# OperantFEDv2.net
KiCad netlist of a schematic drawn in EAGLE
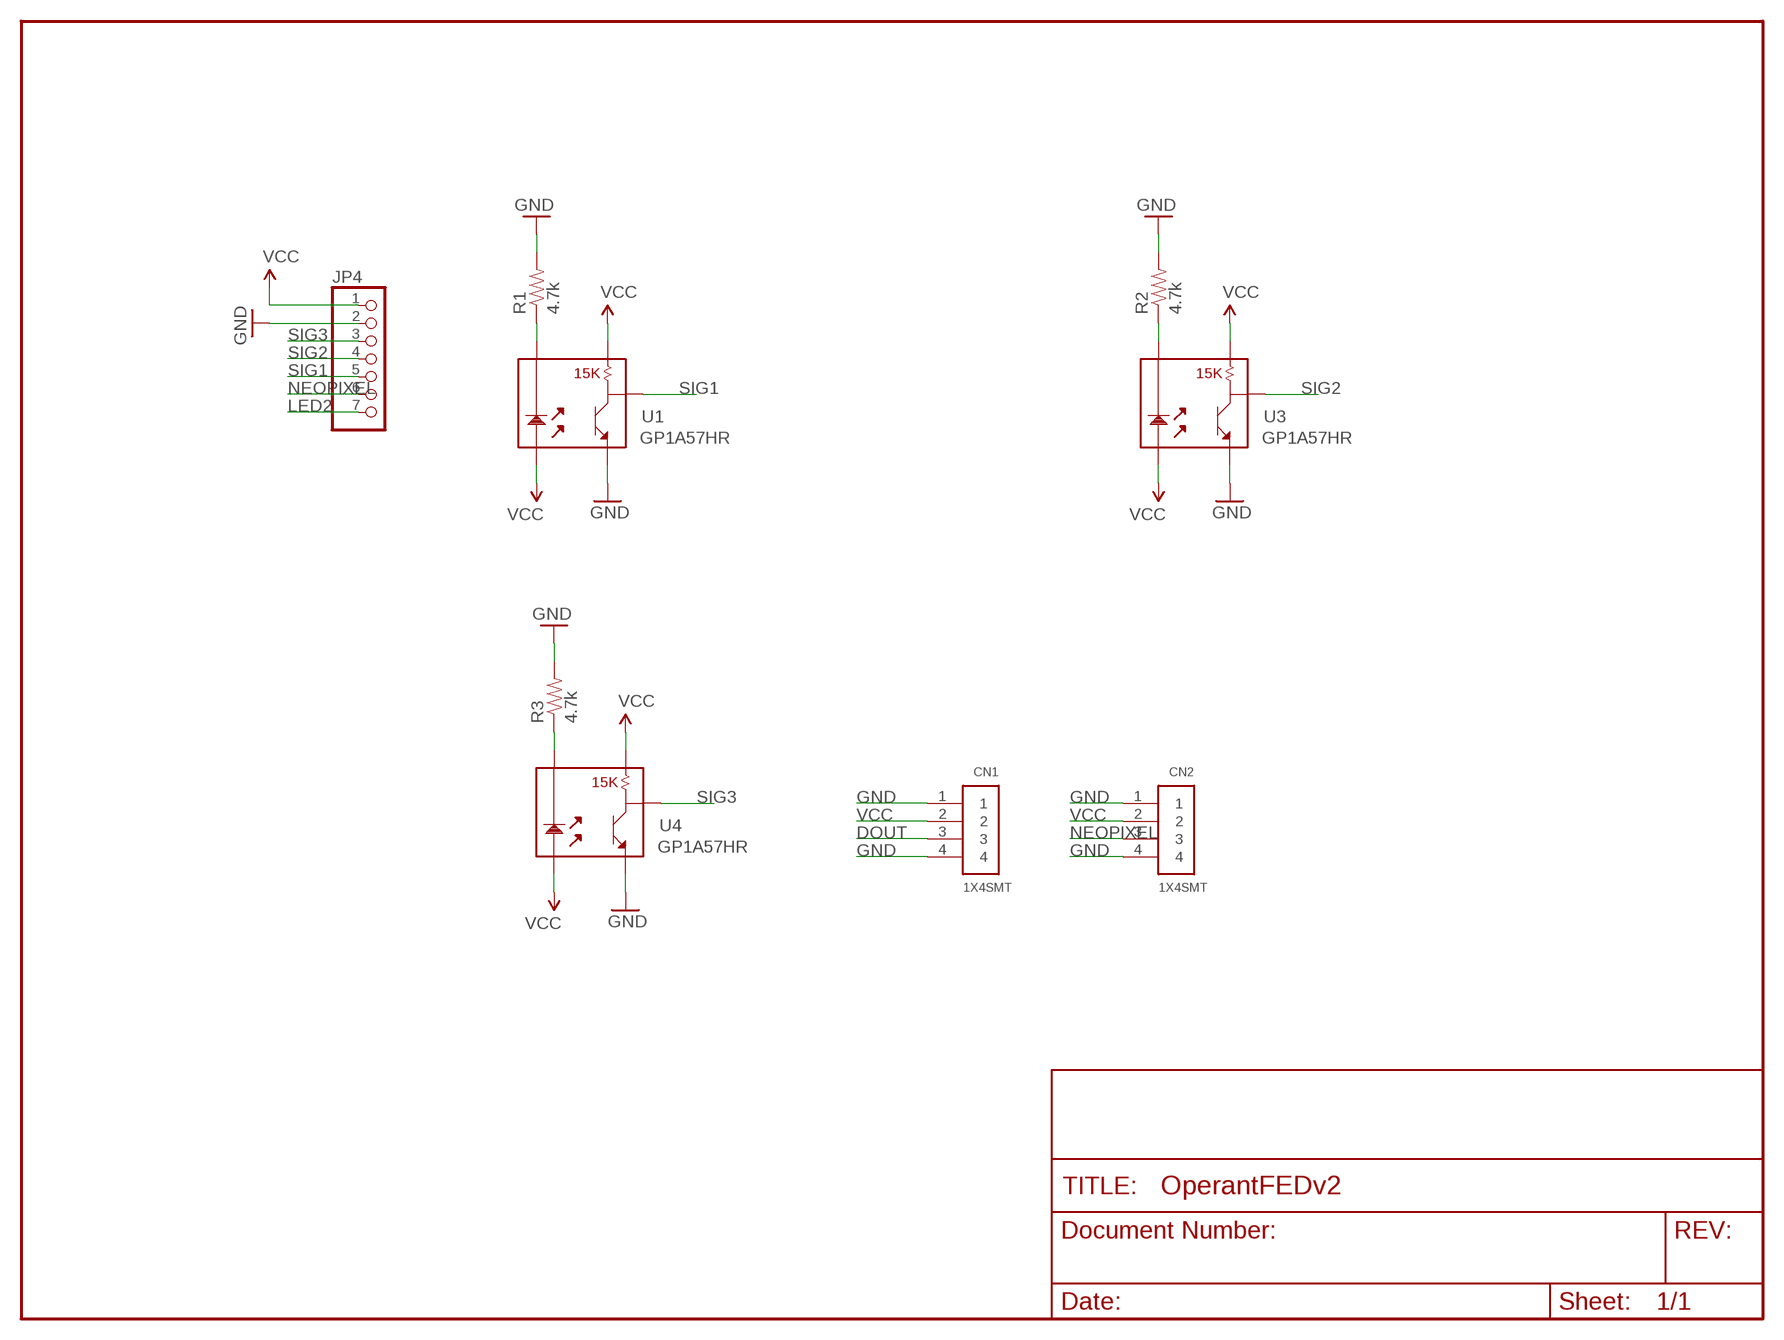
[diagram p0: schematic, sheet 1]

(export (version "E")
  (design (tool "Eeschema 10.0.6"))
  (components
    (comp (ref "CN1")
      (value "1X4SMT")
      (footprint "eagle-import:1X4-SMT")
      (libsource (lib "eagle-import") (part "1X4SMT"))
    )
    (comp (ref "CN2")
      (value "1X4SMT")
      (footprint "eagle-import:1X4-SMT")
      (libsource (lib "eagle-import") (part "1X4SMT"))
    )
    (comp (ref "JP4")
      (value "PINHD-1X7")
      (footprint "eagle-import:1X07")
      (libsource (lib "eagle-import") (part "PINHD-1X7"))
    )
    (comp (ref "R1")
      (value "4.7k")
      (footprint "eagle-import:AXIAL-0.3")
      (libsource (lib "eagle-import") (part "RESISTORPTH1"))
    )
    (comp (ref "R2")
      (value "4.7k")
      (footprint "eagle-import:AXIAL-0.3")
      (libsource (lib "eagle-import") (part "RESISTORPTH1"))
    )
    (comp (ref "R3")
      (value "4.7k")
      (footprint "eagle-import:AXIAL-0.3")
      (libsource (lib "eagle-import") (part "RESISTORPTH1"))
    )
    (comp (ref "U1")
      (value "GP1A57HR")
      (footprint "eagle-import:GP1A57HR")
      (libsource (lib "eagle-import") (part "GP1A57HR"))
    )
    (comp (ref "U3")
      (value "GP1A57HR")
      (footprint "eagle-import:GP1A57HR")
      (libsource (lib "eagle-import") (part "GP1A57HR"))
    )
    (comp (ref "U4")
      (value "GP1A57HR")
      (footprint "eagle-import:GP1A57HR")
      (libsource (lib "eagle-import") (part "GP1A57HR"))
    )
  )
  (nets
    (net (code "1") (name "/DOUT") (class "Default")
      (node (ref "CN1") (pin "3") (pinfunction "3_3") (pintype "bidirectional"))
    )
    (net (code "2") (name "/LED2") (class "Default")
      (node (ref "JP4") (pin "7") (pinfunction "7_7") (pintype "passive"))
    )
    (net (code "3") (name "/NEOPIXEL") (class "Default")
      (node (ref "CN2") (pin "3") (pinfunction "3_3") (pintype "bidirectional"))
      (node (ref "JP4") (pin "6") (pinfunction "6_6") (pintype "passive"))
    )
    (net (code "4") (name "/SIG1") (class "Default")
      (node (ref "JP4") (pin "5") (pinfunction "5_5") (pintype "passive"))
      (node (ref "U1") (pin "4") (pinfunction "4_4") (pintype "bidirectional"))
    )
    (net (code "5") (name "/SIG2") (class "Default")
      (node (ref "JP4") (pin "4") (pinfunction "4_4") (pintype "passive"))
      (node (ref "U3") (pin "4") (pinfunction "4_4") (pintype "bidirectional"))
    )
    (net (code "6") (name "/SIG3") (class "Default")
      (node (ref "JP4") (pin "3") (pinfunction "3_3") (pintype "passive"))
      (node (ref "U4") (pin "4") (pinfunction "4_4") (pintype "bidirectional"))
    )
    (net (code "7") (name "GND") (class "Default")
      (node (ref "CN1") (pin "1") (pinfunction "1_1") (pintype "bidirectional"))
      (node (ref "CN1") (pin "4") (pinfunction "4_4") (pintype "bidirectional"))
      (node (ref "CN2") (pin "1") (pinfunction "1_1") (pintype "bidirectional"))
      (node (ref "CN2") (pin "4") (pinfunction "4_4") (pintype "bidirectional"))
      (node (ref "JP4") (pin "2") (pinfunction "2_2") (pintype "passive"))
      (node (ref "R1") (pin "P$2") (pinfunction "2_P$2") (pintype "passive"))
      (node (ref "R2") (pin "P$2") (pinfunction "2_P$2") (pintype "passive"))
      (node (ref "R3") (pin "P$2") (pinfunction "2_P$2") (pintype "passive"))
      (node (ref "U1") (pin "5") (pinfunction "5_5") (pintype "bidirectional"))
      (node (ref "U3") (pin "5") (pinfunction "5_5") (pintype "bidirectional"))
      (node (ref "U4") (pin "5") (pinfunction "5_5") (pintype "bidirectional"))
    )
    (net (code "8") (name "Net-(R1-1)") (class "Default")
      (node (ref "R1") (pin "P$1") (pinfunction "1_P$1") (pintype "passive"))
      (node (ref "U1") (pin "2") (pinfunction "2_2") (pintype "bidirectional"))
    )
    (net (code "9") (name "Net-(R2-1)") (class "Default")
      (node (ref "R2") (pin "P$1") (pinfunction "1_P$1") (pintype "passive"))
      (node (ref "U3") (pin "2") (pinfunction "2_2") (pintype "bidirectional"))
    )
    (net (code "10") (name "Net-(R3-1)") (class "Default")
      (node (ref "R3") (pin "P$1") (pinfunction "1_P$1") (pintype "passive"))
      (node (ref "U4") (pin "2") (pinfunction "2_2") (pintype "bidirectional"))
    )
    (net (code "11") (name "VCC") (class "Default")
      (node (ref "CN1") (pin "2") (pinfunction "2_2") (pintype "bidirectional"))
      (node (ref "CN2") (pin "2") (pinfunction "2_2") (pintype "bidirectional"))
      (node (ref "JP4") (pin "1") (pinfunction "1_1") (pintype "passive"))
      (node (ref "U1") (pin "1") (pinfunction "1_1") (pintype "bidirectional"))
      (node (ref "U1") (pin "3") (pinfunction "3_3") (pintype "bidirectional"))
      (node (ref "U3") (pin "1") (pinfunction "1_1") (pintype "bidirectional"))
      (node (ref "U3") (pin "3") (pinfunction "3_3") (pintype "bidirectional"))
      (node (ref "U4") (pin "1") (pinfunction "1_1") (pintype "bidirectional"))
      (node (ref "U4") (pin "3") (pinfunction "3_3") (pintype "bidirectional"))
    )
  )
)
